# OutputIndicator.net
KiCad netlist of a schematic drawn in EAGLE
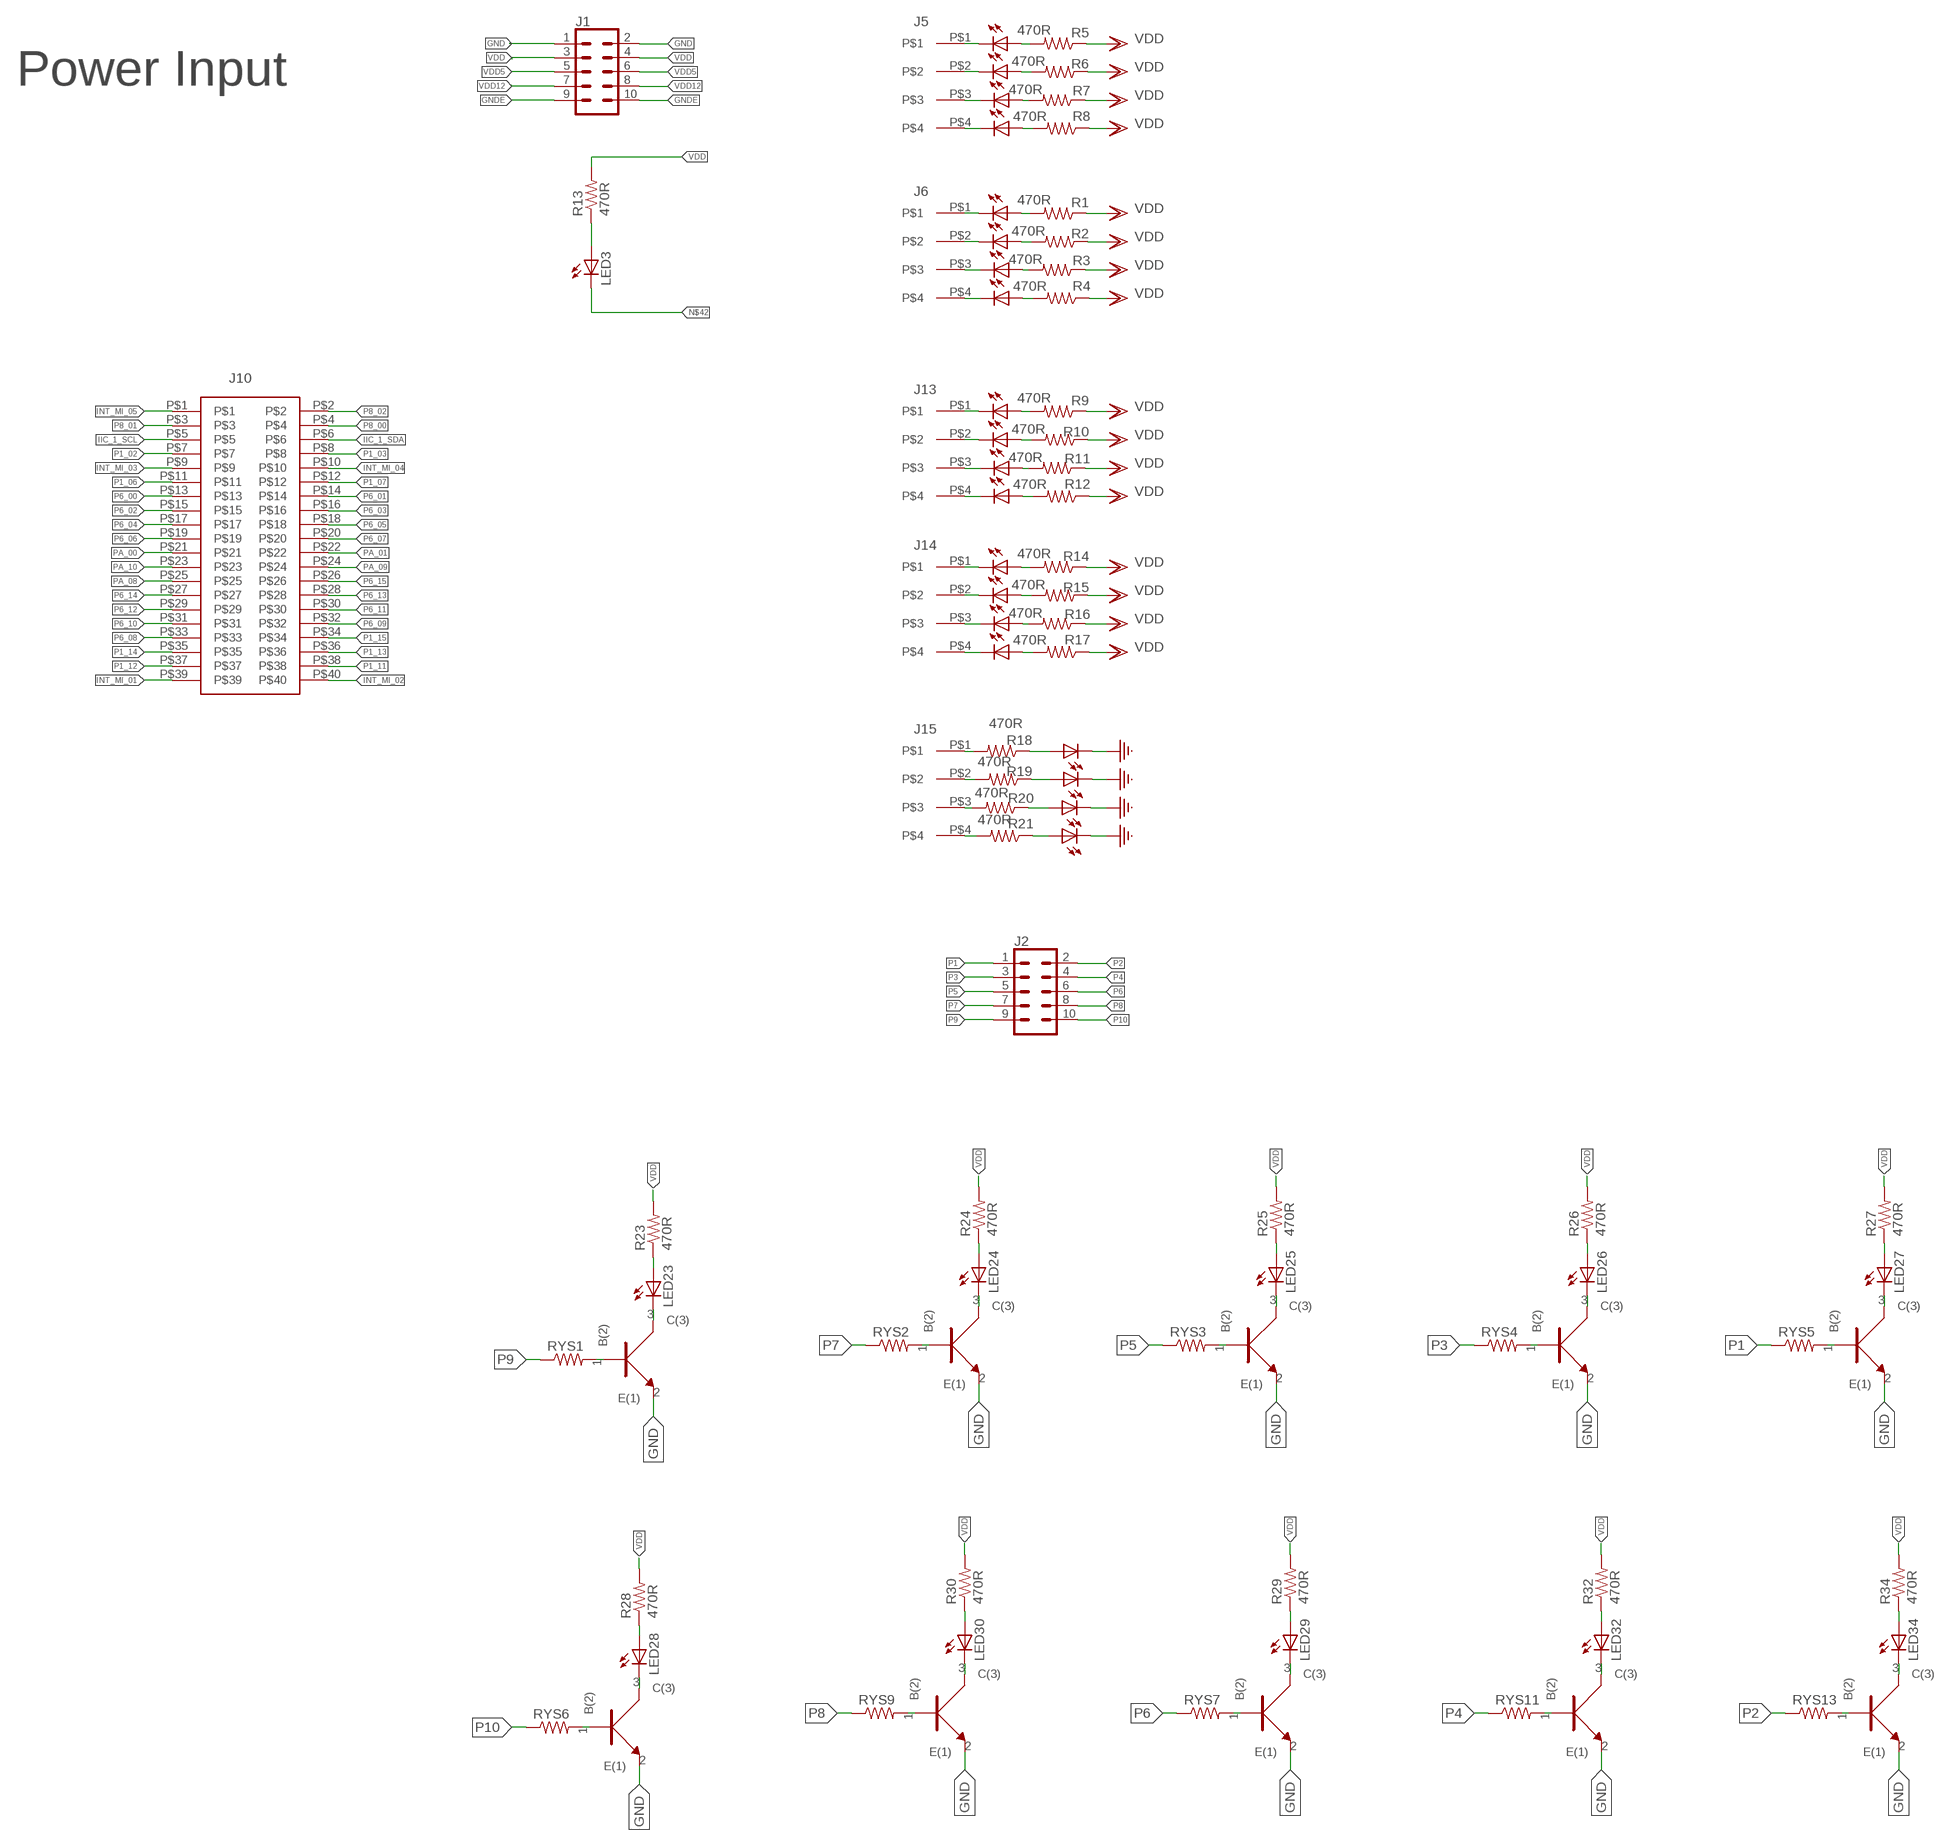
[diagram p0: schematic, sheet 1]

(export (version "E")
  (design (tool "Eeschema 10.0.6"))
  (components
    (comp (ref "J1")
      (value "CONN_05X2PTH")
      (footprint "eagle-import:2X5")
      (libsource (lib "eagle-import") (part "CONN_05X2PTH"))
    )
    (comp (ref "J2")
      (value "CONN_05X2NO_SILK")
      (footprint "eagle-import:2X5_NOSILK")
      (libsource (lib "eagle-import") (part "CONN_05X2NO_SILK"))
    )
    (comp (ref "J5")
      (value "3.81MM_1_X_4_RT_ANGLE_PLUG_HEADER")
      (footprint "eagle-import:1X4_3.81MM_PITCH")
      (libsource (lib "eagle-import") (part "3.81MM_1_X_4_RT_ANGLE_PLUG_HEADER"))
    )
    (comp (ref "J6")
      (value "3.81MM_1_X_4_RT_ANGLE_PLUG_HEADER")
      (footprint "eagle-import:1X4_3.81MM_PITCH")
      (libsource (lib "eagle-import") (part "3.81MM_1_X_4_RT_ANGLE_PLUG_HEADER"))
    )
    (comp (ref "J10")
      (value "HEADER_2_X_20_GENERIC")
      (footprint "eagle-import:HEADER_2_X_20_.1_INCH")
      (libsource (lib "eagle-import") (part "HEADER_2_X_20_GENERIC"))
    )
    (comp (ref "J13")
      (value "3.81MM_1_X_4_RT_ANGLE_PLUG_HEADER")
      (footprint "eagle-import:1X4_3.81MM_PITCH")
      (libsource (lib "eagle-import") (part "3.81MM_1_X_4_RT_ANGLE_PLUG_HEADER"))
    )
    (comp (ref "J14")
      (value "3.81MM_1_X_4_RT_ANGLE_PLUG_HEADER")
      (footprint "eagle-import:1X4_3.81MM_PITCH")
      (libsource (lib "eagle-import") (part "3.81MM_1_X_4_RT_ANGLE_PLUG_HEADER"))
    )
    (comp (ref "J15")
      (value "3.81MM_1_X_4_RT_ANGLE_PLUG_HEADER")
      (footprint "eagle-import:1X4_3.81MM_PITCH")
      (libsource (lib "eagle-import") (part "3.81MM_1_X_4_RT_ANGLE_PLUG_HEADER"))
    )
    (comp (ref "LED1")
      (value "LED_0805_GREEN")
      (footprint "eagle-import:LED_0805_GREEN")
      (libsource (lib "eagle-import") (part "LED_0805_GREEN"))
    )
    (comp (ref "LED2")
      (value "LED_0805_GREEN")
      (footprint "eagle-import:LED_0805_GREEN")
      (libsource (lib "eagle-import") (part "LED_0805_GREEN"))
    )
    (comp (ref "LED3")
      (value "LED_0805_GREEN")
      (footprint "eagle-import:LED_0805_GREEN")
      (libsource (lib "eagle-import") (part "LED_0805_GREEN"))
    )
    (comp (ref "LED4")
      (value "LED_0805_GREEN")
      (footprint "eagle-import:LED_0805_GREEN")
      (libsource (lib "eagle-import") (part "LED_0805_GREEN"))
    )
    (comp (ref "LED5")
      (value "LED_0805_GREEN")
      (footprint "eagle-import:LED_0805_GREEN")
      (libsource (lib "eagle-import") (part "LED_0805_GREEN"))
    )
    (comp (ref "LED6")
      (value "LED_0805_GREEN")
      (footprint "eagle-import:LED_0805_GREEN")
      (libsource (lib "eagle-import") (part "LED_0805_GREEN"))
    )
    (comp (ref "LED7")
      (value "LED_0805_GREEN")
      (footprint "eagle-import:LED_0805_GREEN")
      (libsource (lib "eagle-import") (part "LED_0805_GREEN"))
    )
    (comp (ref "LED8")
      (value "LED_0805_GREEN")
      (footprint "eagle-import:LED_0805_GREEN")
      (libsource (lib "eagle-import") (part "LED_0805_GREEN"))
    )
    (comp (ref "LED9")
      (value "LED_0805_GREEN")
      (footprint "eagle-import:LED_0805_GREEN")
      (libsource (lib "eagle-import") (part "LED_0805_GREEN"))
    )
    (comp (ref "LED10")
      (value "LED_0805_GREEN")
      (footprint "eagle-import:LED_0805_GREEN")
      (libsource (lib "eagle-import") (part "LED_0805_GREEN"))
    )
    (comp (ref "LED11")
      (value "LED_0805_GREEN")
      (footprint "eagle-import:LED_0805_GREEN")
      (libsource (lib "eagle-import") (part "LED_0805_GREEN"))
    )
    (comp (ref "LED12")
      (value "LED_0805_GREEN")
      (footprint "eagle-import:LED_0805_GREEN")
      (libsource (lib "eagle-import") (part "LED_0805_GREEN"))
    )
    (comp (ref "LED13")
      (value "LED_0805_GREEN")
      (footprint "eagle-import:LED_0805_GREEN")
      (libsource (lib "eagle-import") (part "LED_0805_GREEN"))
    )
    (comp (ref "LED14")
      (value "LED_0805_GREEN")
      (footprint "eagle-import:LED_0805_GREEN")
      (libsource (lib "eagle-import") (part "LED_0805_GREEN"))
    )
    (comp (ref "LED15")
      (value "LED_0805_GREEN")
      (footprint "eagle-import:LED_0805_GREEN")
      (libsource (lib "eagle-import") (part "LED_0805_GREEN"))
    )
    (comp (ref "LED16")
      (value "LED_0805_GREEN")
      (footprint "eagle-import:LED_0805_GREEN")
      (libsource (lib "eagle-import") (part "LED_0805_GREEN"))
    )
    (comp (ref "LED17")
      (value "LED_0805_GREEN")
      (footprint "eagle-import:LED_0805_GREEN")
      (libsource (lib "eagle-import") (part "LED_0805_GREEN"))
    )
    (comp (ref "LED18")
      (value "LED_0805_GREEN")
      (footprint "eagle-import:LED_0805_GREEN")
      (libsource (lib "eagle-import") (part "LED_0805_GREEN"))
    )
    (comp (ref "LED19")
      (value "LED_0805_GREEN")
      (footprint "eagle-import:LED_0805_GREEN")
      (libsource (lib "eagle-import") (part "LED_0805_GREEN"))
    )
    (comp (ref "LED20")
      (value "LED_0805_GREEN")
      (footprint "eagle-import:LED_0805_GREEN")
      (libsource (lib "eagle-import") (part "LED_0805_GREEN"))
    )
    (comp (ref "LED21")
      (value "LED_0805_GREEN")
      (footprint "eagle-import:LED_0805_GREEN")
      (libsource (lib "eagle-import") (part "LED_0805_GREEN"))
    )
    (comp (ref "LED23")
      (value "LED_0805_GREEN")
      (footprint "eagle-import:LED_0805_GREEN")
      (libsource (lib "eagle-import") (part "LED_0805_GREEN"))
    )
    (comp (ref "LED24")
      (value "LED_0805_GREEN")
      (footprint "eagle-import:LED_0805_GREEN")
      (libsource (lib "eagle-import") (part "LED_0805_GREEN"))
    )
    (comp (ref "LED25")
      (value "LED_0805_GREEN")
      (footprint "eagle-import:LED_0805_GREEN")
      (libsource (lib "eagle-import") (part "LED_0805_GREEN"))
    )
    (comp (ref "LED26")
      (value "LED_0805_GREEN")
      (footprint "eagle-import:LED_0805_GREEN")
      (libsource (lib "eagle-import") (part "LED_0805_GREEN"))
    )
    (comp (ref "LED27")
      (value "LED_0805_GREEN")
      (footprint "eagle-import:LED_0805_GREEN")
      (libsource (lib "eagle-import") (part "LED_0805_GREEN"))
    )
    (comp (ref "LED28")
      (value "LED_0805_GREEN")
      (footprint "eagle-import:LED_0805_GREEN")
      (libsource (lib "eagle-import") (part "LED_0805_GREEN"))
    )
    (comp (ref "LED29")
      (value "LED_0805_GREEN")
      (footprint "eagle-import:LED_0805_GREEN")
      (libsource (lib "eagle-import") (part "LED_0805_GREEN"))
    )
    (comp (ref "LED30")
      (value "LED_0805_GREEN")
      (footprint "eagle-import:LED_0805_GREEN")
      (libsource (lib "eagle-import") (part "LED_0805_GREEN"))
    )
    (comp (ref "LED32")
      (value "LED_0805_GREEN")
      (footprint "eagle-import:LED_0805_GREEN")
      (libsource (lib "eagle-import") (part "LED_0805_GREEN"))
    )
    (comp (ref "LED34")
      (value "LED_0805_GREEN")
      (footprint "eagle-import:LED_0805_GREEN")
      (libsource (lib "eagle-import") (part "LED_0805_GREEN"))
    )
    (comp (ref "R1")
      (value "470R")
      (footprint "eagle-import:0402")
      (libsource (lib "eagle-import") (part "R_0402"))
    )
    (comp (ref "R2")
      (value "470R")
      (footprint "eagle-import:0402")
      (libsource (lib "eagle-import") (part "R_0402"))
    )
    (comp (ref "R3")
      (value "470R")
      (footprint "eagle-import:0402")
      (libsource (lib "eagle-import") (part "R_0402"))
    )
    (comp (ref "R4")
      (value "470R")
      (footprint "eagle-import:0402")
      (libsource (lib "eagle-import") (part "R_0402"))
    )
    (comp (ref "R5")
      (value "470R")
      (footprint "eagle-import:0402")
      (libsource (lib "eagle-import") (part "R_0402"))
    )
    (comp (ref "R6")
      (value "470R")
      (footprint "eagle-import:0402")
      (libsource (lib "eagle-import") (part "R_0402"))
    )
    (comp (ref "R7")
      (value "470R")
      (footprint "eagle-import:0402")
      (libsource (lib "eagle-import") (part "R_0402"))
    )
    (comp (ref "R8")
      (value "470R")
      (footprint "eagle-import:0402")
      (libsource (lib "eagle-import") (part "R_0402"))
    )
    (comp (ref "R9")
      (value "470R")
      (footprint "eagle-import:0402")
      (libsource (lib "eagle-import") (part "R_0402"))
    )
    (comp (ref "R10")
      (value "470R")
      (footprint "eagle-import:0402")
      (libsource (lib "eagle-import") (part "R_0402"))
    )
    (comp (ref "R11")
      (value "470R")
      (footprint "eagle-import:0402")
      (libsource (lib "eagle-import") (part "R_0402"))
    )
    (comp (ref "R12")
      (value "470R")
      (footprint "eagle-import:0402")
      (libsource (lib "eagle-import") (part "R_0402"))
    )
    (comp (ref "R13")
      (value "470R")
      (footprint "eagle-import:0402")
      (libsource (lib "eagle-import") (part "R_0402"))
    )
    (comp (ref "R14")
      (value "470R")
      (footprint "eagle-import:0402")
      (libsource (lib "eagle-import") (part "R_0402"))
    )
    (comp (ref "R15")
      (value "470R")
      (footprint "eagle-import:0402")
      (libsource (lib "eagle-import") (part "R_0402"))
    )
    (comp (ref "R16")
      (value "470R")
      (footprint "eagle-import:0402")
      (libsource (lib "eagle-import") (part "R_0402"))
    )
    (comp (ref "R17")
      (value "470R")
      (footprint "eagle-import:0402")
      (libsource (lib "eagle-import") (part "R_0402"))
    )
    (comp (ref "R18")
      (value "470R")
      (footprint "eagle-import:0402")
      (libsource (lib "eagle-import") (part "R_0402"))
    )
    (comp (ref "R19")
      (value "470R")
      (footprint "eagle-import:0402")
      (libsource (lib "eagle-import") (part "R_0402"))
    )
    (comp (ref "R20")
      (value "470R")
      (footprint "eagle-import:0402")
      (libsource (lib "eagle-import") (part "R_0402"))
    )
    (comp (ref "R21")
      (value "470R")
      (footprint "eagle-import:0402")
      (libsource (lib "eagle-import") (part "R_0402"))
    )
    (comp (ref "R23")
      (value "470R")
      (footprint "eagle-import:0402")
      (libsource (lib "eagle-import") (part "R_0402"))
    )
    (comp (ref "R24")
      (value "470R")
      (footprint "eagle-import:0402")
      (libsource (lib "eagle-import") (part "R_0402"))
    )
    (comp (ref "R25")
      (value "470R")
      (footprint "eagle-import:0402")
      (libsource (lib "eagle-import") (part "R_0402"))
    )
    (comp (ref "R26")
      (value "470R")
      (footprint "eagle-import:0402")
      (libsource (lib "eagle-import") (part "R_0402"))
    )
    (comp (ref "R27")
      (value "470R")
      (footprint "eagle-import:0402")
      (libsource (lib "eagle-import") (part "R_0402"))
    )
    (comp (ref "R28")
      (value "470R")
      (footprint "eagle-import:0402")
      (libsource (lib "eagle-import") (part "R_0402"))
    )
    (comp (ref "R29")
      (value "470R")
      (footprint "eagle-import:0402")
      (libsource (lib "eagle-import") (part "R_0402"))
    )
    (comp (ref "R30")
      (value "470R")
      (footprint "eagle-import:0402")
      (libsource (lib "eagle-import") (part "R_0402"))
    )
    (comp (ref "R32")
      (value "470R")
      (footprint "eagle-import:0402")
      (libsource (lib "eagle-import") (part "R_0402"))
    )
    (comp (ref "R34")
      (value "470R")
      (footprint "eagle-import:0402")
      (libsource (lib "eagle-import") (part "R_0402"))
    )
    (comp (ref "RYS1")
      (value "1K")
      (footprint "eagle-import:0402")
      (libsource (lib "eagle-import") (part "R_0402"))
    )
    (comp (ref "RYS2")
      (value "1K")
      (footprint "eagle-import:0402")
      (libsource (lib "eagle-import") (part "R_0402"))
    )
    (comp (ref "RYS3")
      (value "1K")
      (footprint "eagle-import:0402")
      (libsource (lib "eagle-import") (part "R_0402"))
    )
    (comp (ref "RYS4")
      (value "1K")
      (footprint "eagle-import:0402")
      (libsource (lib "eagle-import") (part "R_0402"))
    )
    (comp (ref "RYS5")
      (value "1K")
      (footprint "eagle-import:0402")
      (libsource (lib "eagle-import") (part "R_0402"))
    )
    (comp (ref "RYS6")
      (value "1K")
      (footprint "eagle-import:0402")
      (libsource (lib "eagle-import") (part "R_0402"))
    )
    (comp (ref "RYS7")
      (value "1K")
      (footprint "eagle-import:0402")
      (libsource (lib "eagle-import") (part "R_0402"))
    )
    (comp (ref "RYS9")
      (value "1K")
      (footprint "eagle-import:0402")
      (libsource (lib "eagle-import") (part "R_0402"))
    )
    (comp (ref "RYS11")
      (value "1K")
      (footprint "eagle-import:0402")
      (libsource (lib "eagle-import") (part "R_0402"))
    )
    (comp (ref "RYS13")
      (value "1K")
      (footprint "eagle-import:0402")
      (libsource (lib "eagle-import") (part "R_0402"))
    )
    (comp (ref "U1")
      (value "BC846BW")
      (footprint "eagle-import:SOT323")
      (libsource (lib "eagle-import") (part "BC846BW"))
    )
    (comp (ref "U2")
      (value "BC846BW")
      (footprint "eagle-import:SOT323")
      (libsource (lib "eagle-import") (part "BC846BW"))
    )
    (comp (ref "U3")
      (value "BC846BW")
      (footprint "eagle-import:SOT323")
      (libsource (lib "eagle-import") (part "BC846BW"))
    )
    (comp (ref "U4")
      (value "BC846BW")
      (footprint "eagle-import:SOT323")
      (libsource (lib "eagle-import") (part "BC846BW"))
    )
    (comp (ref "U5")
      (value "BC846BW")
      (footprint "eagle-import:SOT323")
      (libsource (lib "eagle-import") (part "BC846BW"))
    )
    (comp (ref "U6")
      (value "BC846BW")
      (footprint "eagle-import:SOT323")
      (libsource (lib "eagle-import") (part "BC846BW"))
    )
    (comp (ref "U7")
      (value "BC846BW")
      (footprint "eagle-import:SOT323")
      (libsource (lib "eagle-import") (part "BC846BW"))
    )
    (comp (ref "U8")
      (value "BC846BW")
      (footprint "eagle-import:SOT323")
      (libsource (lib "eagle-import") (part "BC846BW"))
    )
    (comp (ref "U10")
      (value "BC846BW")
      (footprint "eagle-import:SOT323")
      (libsource (lib "eagle-import") (part "BC846BW"))
    )
    (comp (ref "U12")
      (value "BC846BW")
      (footprint "eagle-import:SOT323")
      (libsource (lib "eagle-import") (part "BC846BW"))
    )
  )
  (nets
    (net (code "1") (name "GND") (class "Default")
      (node (ref "J1") (pin "1") (pinfunction "1_1") (pintype "passive"))
      (node (ref "J1") (pin "2") (pinfunction "2_2") (pintype "passive"))
      (node (ref "LED18") (pin "C") (pinfunction "C_C") (pintype "passive"))
      (node (ref "LED19") (pin "C") (pinfunction "C_C") (pintype "passive"))
      (node (ref "LED20") (pin "C") (pinfunction "C_C") (pintype "passive"))
      (node (ref "LED21") (pin "C") (pinfunction "C_C") (pintype "passive"))
      (node (ref "U1") (pin "2") (pinfunction "E(1)_2") (pintype "output"))
      (node (ref "U10") (pin "2") (pinfunction "E(1)_2") (pintype "output"))
      (node (ref "U12") (pin "2") (pinfunction "E(1)_2") (pintype "output"))
      (node (ref "U2") (pin "2") (pinfunction "E(1)_2") (pintype "output"))
      (node (ref "U3") (pin "2") (pinfunction "E(1)_2") (pintype "output"))
      (node (ref "U4") (pin "2") (pinfunction "E(1)_2") (pintype "output"))
      (node (ref "U5") (pin "2") (pinfunction "E(1)_2") (pintype "output"))
      (node (ref "U6") (pin "2") (pinfunction "E(1)_2") (pintype "output"))
      (node (ref "U7") (pin "2") (pinfunction "E(1)_2") (pintype "output"))
      (node (ref "U8") (pin "2") (pinfunction "E(1)_2") (pintype "output"))
    )
    (net (code "2") (name "GNDE") (class "Default")
      (node (ref "J1") (pin "10") (pinfunction "10_10") (pintype "passive"))
      (node (ref "J1") (pin "9") (pinfunction "9_9") (pintype "passive"))
    )
    (net (code "3") (name "IIC_1_SCL") (class "Default")
      (node (ref "J10") (pin "P$5") (pinfunction "P$5_P$5") (pintype "bidirectional"))
    )
    (net (code "4") (name "IIC_1_SDA") (class "Default")
      (node (ref "J10") (pin "P$6") (pinfunction "P$6_P$6") (pintype "bidirectional"))
    )
    (net (code "5") (name "INT_MI_01") (class "Default")
      (node (ref "J10") (pin "P$39") (pinfunction "P$39_P$39") (pintype "bidirectional"))
    )
    (net (code "6") (name "INT_MI_02") (class "Default")
      (node (ref "J10") (pin "P$40") (pinfunction "P$40_P$40") (pintype "bidirectional"))
    )
    (net (code "7") (name "INT_MI_03") (class "Default")
      (node (ref "J10") (pin "P$9") (pinfunction "P$9_P$9") (pintype "bidirectional"))
    )
    (net (code "8") (name "INT_MI_04") (class "Default")
      (node (ref "J10") (pin "P$10") (pinfunction "P$10_P$10") (pintype "bidirectional"))
    )
    (net (code "9") (name "INT_MI_05") (class "Default")
      (node (ref "J10") (pin "P$1") (pinfunction "P$1_P$1") (pintype "bidirectional"))
    )
    (net (code "10") (name "N$42") (class "Default")
      (node (ref "LED3") (pin "C") (pinfunction "C_C") (pintype "passive"))
    )
    (net (code "11") (name "Net-(J5-PadP$1)") (class "Default")
      (node (ref "J5") (pin "P$1") (pinfunction "P$1_P$1") (pintype "bidirectional"))
      (node (ref "LED6") (pin "C") (pinfunction "C_C") (pintype "passive"))
    )
    (net (code "12") (name "Net-(J5-PadP$2)") (class "Default")
      (node (ref "J5") (pin "P$2") (pinfunction "P$2_P$2") (pintype "bidirectional"))
      (node (ref "LED7") (pin "C") (pinfunction "C_C") (pintype "passive"))
    )
    (net (code "13") (name "Net-(J5-PadP$3)") (class "Default")
      (node (ref "J5") (pin "P$3") (pinfunction "P$3_P$3") (pintype "bidirectional"))
      (node (ref "LED8") (pin "C") (pinfunction "C_C") (pintype "passive"))
    )
    (net (code "14") (name "Net-(J5-PadP$4)") (class "Default")
      (node (ref "J5") (pin "P$4") (pinfunction "P$4_P$4") (pintype "bidirectional"))
      (node (ref "LED9") (pin "C") (pinfunction "C_C") (pintype "passive"))
    )
    (net (code "15") (name "Net-(J6-PadP$1)") (class "Default")
      (node (ref "J6") (pin "P$1") (pinfunction "P$1_P$1") (pintype "bidirectional"))
      (node (ref "LED1") (pin "C") (pinfunction "C_C") (pintype "passive"))
    )
    (net (code "16") (name "Net-(J6-PadP$2)") (class "Default")
      (node (ref "J6") (pin "P$2") (pinfunction "P$2_P$2") (pintype "bidirectional"))
      (node (ref "LED2") (pin "C") (pinfunction "C_C") (pintype "passive"))
    )
    (net (code "17") (name "Net-(J6-PadP$3)") (class "Default")
      (node (ref "J6") (pin "P$3") (pinfunction "P$3_P$3") (pintype "bidirectional"))
      (node (ref "LED4") (pin "C") (pinfunction "C_C") (pintype "passive"))
    )
    (net (code "18") (name "Net-(J6-PadP$4)") (class "Default")
      (node (ref "J6") (pin "P$4") (pinfunction "P$4_P$4") (pintype "bidirectional"))
      (node (ref "LED5") (pin "C") (pinfunction "C_C") (pintype "passive"))
    )
    (net (code "19") (name "Net-(J13-PadP$1)") (class "Default")
      (node (ref "J13") (pin "P$1") (pinfunction "P$1_P$1") (pintype "bidirectional"))
      (node (ref "LED10") (pin "C") (pinfunction "C_C") (pintype "passive"))
    )
    (net (code "20") (name "Net-(J13-PadP$2)") (class "Default")
      (node (ref "J13") (pin "P$2") (pinfunction "P$2_P$2") (pintype "bidirectional"))
      (node (ref "LED11") (pin "C") (pinfunction "C_C") (pintype "passive"))
    )
    (net (code "21") (name "Net-(J13-PadP$3)") (class "Default")
      (node (ref "J13") (pin "P$3") (pinfunction "P$3_P$3") (pintype "bidirectional"))
      (node (ref "LED12") (pin "C") (pinfunction "C_C") (pintype "passive"))
    )
    (net (code "22") (name "Net-(J13-PadP$4)") (class "Default")
      (node (ref "J13") (pin "P$4") (pinfunction "P$4_P$4") (pintype "bidirectional"))
      (node (ref "LED13") (pin "C") (pinfunction "C_C") (pintype "passive"))
    )
    (net (code "23") (name "Net-(J14-PadP$1)") (class "Default")
      (node (ref "J14") (pin "P$1") (pinfunction "P$1_P$1") (pintype "bidirectional"))
      (node (ref "LED14") (pin "C") (pinfunction "C_C") (pintype "passive"))
    )
    (net (code "24") (name "Net-(J14-PadP$2)") (class "Default")
      (node (ref "J14") (pin "P$2") (pinfunction "P$2_P$2") (pintype "bidirectional"))
      (node (ref "LED15") (pin "C") (pinfunction "C_C") (pintype "passive"))
    )
    (net (code "25") (name "Net-(J14-PadP$3)") (class "Default")
      (node (ref "J14") (pin "P$3") (pinfunction "P$3_P$3") (pintype "bidirectional"))
      (node (ref "LED16") (pin "C") (pinfunction "C_C") (pintype "passive"))
    )
    (net (code "26") (name "Net-(J14-PadP$4)") (class "Default")
      (node (ref "J14") (pin "P$4") (pinfunction "P$4_P$4") (pintype "bidirectional"))
      (node (ref "LED17") (pin "C") (pinfunction "C_C") (pintype "passive"))
    )
    (net (code "27") (name "Net-(R1-2)") (class "Default")
      (node (ref "LED1") (pin "A") (pinfunction "A_A") (pintype "passive"))
      (node (ref "R1") (pin "P$2") (pinfunction "2_P$2") (pintype "passive"))
    )
    (net (code "28") (name "Net-(R2-2)") (class "Default")
      (node (ref "LED2") (pin "A") (pinfunction "A_A") (pintype "passive"))
      (node (ref "R2") (pin "P$2") (pinfunction "2_P$2") (pintype "passive"))
    )
    (net (code "29") (name "Net-(R3-2)") (class "Default")
      (node (ref "LED4") (pin "A") (pinfunction "A_A") (pintype "passive"))
      (node (ref "R3") (pin "P$2") (pinfunction "2_P$2") (pintype "passive"))
    )
    (net (code "30") (name "Net-(R4-2)") (class "Default")
      (node (ref "LED5") (pin "A") (pinfunction "A_A") (pintype "passive"))
      (node (ref "R4") (pin "P$2") (pinfunction "2_P$2") (pintype "passive"))
    )
    (net (code "31") (name "Net-(R5-2)") (class "Default")
      (node (ref "LED6") (pin "A") (pinfunction "A_A") (pintype "passive"))
      (node (ref "R5") (pin "P$2") (pinfunction "2_P$2") (pintype "passive"))
    )
    (net (code "32") (name "Net-(R6-2)") (class "Default")
      (node (ref "LED7") (pin "A") (pinfunction "A_A") (pintype "passive"))
      (node (ref "R6") (pin "P$2") (pinfunction "2_P$2") (pintype "passive"))
    )
    (net (code "33") (name "Net-(R7-2)") (class "Default")
      (node (ref "LED8") (pin "A") (pinfunction "A_A") (pintype "passive"))
      (node (ref "R7") (pin "P$2") (pinfunction "2_P$2") (pintype "passive"))
    )
    (net (code "34") (name "Net-(R8-2)") (class "Default")
      (node (ref "LED9") (pin "A") (pinfunction "A_A") (pintype "passive"))
      (node (ref "R8") (pin "P$2") (pinfunction "2_P$2") (pintype "passive"))
    )
    (net (code "35") (name "Net-(R9-2)") (class "Default")
      (node (ref "LED10") (pin "A") (pinfunction "A_A") (pintype "passive"))
      (node (ref "R9") (pin "P$2") (pinfunction "2_P$2") (pintype "passive"))
    )
    (net (code "36") (name "Net-(R10-2)") (class "Default")
      (node (ref "LED11") (pin "A") (pinfunction "A_A") (pintype "passive"))
      (node (ref "R10") (pin "P$2") (pinfunction "2_P$2") (pintype "passive"))
    )
    (net (code "37") (name "Net-(R11-2)") (class "Default")
      (node (ref "LED12") (pin "A") (pinfunction "A_A") (pintype "passive"))
      (node (ref "R11") (pin "P$2") (pinfunction "2_P$2") (pintype "passive"))
    )
    (net (code "38") (name "Net-(R12-2)") (class "Default")
      (node (ref "LED13") (pin "A") (pinfunction "A_A") (pintype "passive"))
      (node (ref "R12") (pin "P$2") (pinfunction "2_P$2") (pintype "passive"))
    )
    (net (code "39") (name "Net-(R13-1)") (class "Default")
      (node (ref "LED3") (pin "A") (pinfunction "A_A") (pintype "passive"))
      (node (ref "R13") (pin "P$1") (pinfunction "1_P$1") (pintype "passive"))
    )
    (net (code "40") (name "Net-(R14-2)") (class "Default")
      (node (ref "LED14") (pin "A") (pinfunction "A_A") (pintype "passive"))
      (node (ref "R14") (pin "P$2") (pinfunction "2_P$2") (pintype "passive"))
    )
    (net (code "41") (name "Net-(R15-2)") (class "Default")
      (node (ref "LED15") (pin "A") (pinfunction "A_A") (pintype "passive"))
      (node (ref "R15") (pin "P$2") (pinfunction "2_P$2") (pintype "passive"))
    )
    (net (code "42") (name "Net-(R16-2)") (class "Default")
      (node (ref "LED16") (pin "A") (pinfunction "A_A") (pintype "passive"))
      (node (ref "R16") (pin "P$2") (pinfunction "2_P$2") (pintype "passive"))
    )
    (net (code "43") (name "Net-(R17-2)") (class "Default")
      (node (ref "LED17") (pin "A") (pinfunction "A_A") (pintype "passive"))
      (node (ref "R17") (pin "P$2") (pinfunction "2_P$2") (pintype "passive"))
    )
    (net (code "44") (name "Net-(R18-1)") (class "Default")
      (node (ref "LED18") (pin "A") (pinfunction "A_A") (pintype "passive"))
      (node (ref "R18") (pin "P$1") (pinfunction "1_P$1") (pintype "passive"))
    )
    (net (code "45") (name "Net-(R18-2)") (class "Default")
      (node (ref "J15") (pin "P$1") (pinfunction "P$1_P$1") (pintype "bidirectional"))
      (node (ref "R18") (pin "P$2") (pinfunction "2_P$2") (pintype "passive"))
    )
    (net (code "46") (name "Net-(R19-1)") (class "Default")
      (node (ref "LED19") (pin "A") (pinfunction "A_A") (pintype "passive"))
      (node (ref "R19") (pin "P$1") (pinfunction "1_P$1") (pintype "passive"))
    )
    (net (code "47") (name "Net-(R19-2)") (class "Default")
      (node (ref "J15") (pin "P$2") (pinfunction "P$2_P$2") (pintype "bidirectional"))
      (node (ref "R19") (pin "P$2") (pinfunction "2_P$2") (pintype "passive"))
    )
    (net (code "48") (name "Net-(R20-1)") (class "Default")
      (node (ref "LED20") (pin "A") (pinfunction "A_A") (pintype "passive"))
      (node (ref "R20") (pin "P$1") (pinfunction "1_P$1") (pintype "passive"))
    )
    (net (code "49") (name "Net-(R20-2)") (class "Default")
      (node (ref "J15") (pin "P$3") (pinfunction "P$3_P$3") (pintype "bidirectional"))
      (node (ref "R20") (pin "P$2") (pinfunction "2_P$2") (pintype "passive"))
    )
    (net (code "50") (name "Net-(R21-1)") (class "Default")
      (node (ref "LED21") (pin "A") (pinfunction "A_A") (pintype "passive"))
      (node (ref "R21") (pin "P$1") (pinfunction "1_P$1") (pintype "passive"))
    )
    (net (code "51") (name "Net-(R21-2)") (class "Default")
      (node (ref "J15") (pin "P$4") (pinfunction "P$4_P$4") (pintype "bidirectional"))
      (node (ref "R21") (pin "P$2") (pinfunction "2_P$2") (pintype "passive"))
    )
    (net (code "52") (name "Net-(R23-1)") (class "Default")
      (node (ref "LED23") (pin "A") (pinfunction "A_A") (pintype "passive"))
      (node (ref "R23") (pin "P$1") (pinfunction "1_P$1") (pintype "passive"))
    )
    (net (code "53") (name "Net-(R24-1)") (class "Default")
      (node (ref "LED24") (pin "A") (pinfunction "A_A") (pintype "passive"))
      (node (ref "R24") (pin "P$1") (pinfunction "1_P$1") (pintype "passive"))
    )
    (net (code "54") (name "Net-(R25-1)") (class "Default")
      (node (ref "LED25") (pin "A") (pinfunction "A_A") (pintype "passive"))
      (node (ref "R25") (pin "P$1") (pinfunction "1_P$1") (pintype "passive"))
    )
    (net (code "55") (name "Net-(R26-1)") (class "Default")
      (node (ref "LED26") (pin "A") (pinfunction "A_A") (pintype "passive"))
      (node (ref "R26") (pin "P$1") (pinfunction "1_P$1") (pintype "passive"))
    )
    (net (code "56") (name "Net-(R27-1)") (class "Default")
      (node (ref "LED27") (pin "A") (pinfunction "A_A") (pintype "passive"))
      (node (ref "R27") (pin "P$1") (pinfunction "1_P$1") (pintype "passive"))
    )
    (net (code "57") (name "Net-(R28-1)") (class "Default")
      (node (ref "LED28") (pin "A") (pinfunction "A_A") (pintype "passive"))
      (node (ref "R28") (pin "P$1") (pinfunction "1_P$1") (pintype "passive"))
    )
    (net (code "58") (name "Net-(R29-1)") (class "Default")
      (node (ref "LED29") (pin "A") (pinfunction "A_A") (pintype "passive"))
      (node (ref "R29") (pin "P$1") (pinfunction "1_P$1") (pintype "passive"))
    )
    (net (code "59") (name "Net-(R30-1)") (class "Default")
      (node (ref "LED30") (pin "A") (pinfunction "A_A") (pintype "passive"))
      (node (ref "R30") (pin "P$1") (pinfunction "1_P$1") (pintype "passive"))
    )
    (net (code "60") (name "Net-(R32-1)") (class "Default")
      (node (ref "LED32") (pin "A") (pinfunction "A_A") (pintype "passive"))
      (node (ref "R32") (pin "P$1") (pinfunction "1_P$1") (pintype "passive"))
    )
    (net (code "61") (name "Net-(R34-1)") (class "Default")
      (node (ref "LED34") (pin "A") (pinfunction "A_A") (pintype "passive"))
      (node (ref "R34") (pin "P$1") (pinfunction "1_P$1") (pintype "passive"))
    )
    (net (code "62") (name "Net-(RYS1-2)") (class "Default")
      (node (ref "RYS1") (pin "P$2") (pinfunction "2_P$2") (pintype "passive"))
      (node (ref "U1") (pin "1") (pinfunction "B(2)_1") (pintype "input"))
    )
    (net (code "63") (name "Net-(RYS2-2)") (class "Default")
      (node (ref "RYS2") (pin "P$2") (pinfunction "2_P$2") (pintype "passive"))
      (node (ref "U2") (pin "1") (pinfunction "B(2)_1") (pintype "input"))
    )
    (net (code "64") (name "Net-(RYS3-2)") (class "Default")
      (node (ref "RYS3") (pin "P$2") (pinfunction "2_P$2") (pintype "passive"))
      (node (ref "U3") (pin "1") (pinfunction "B(2)_1") (pintype "input"))
    )
    (net (code "65") (name "Net-(RYS4-2)") (class "Default")
      (node (ref "RYS4") (pin "P$2") (pinfunction "2_P$2") (pintype "passive"))
      (node (ref "U4") (pin "1") (pinfunction "B(2)_1") (pintype "input"))
    )
    (net (code "66") (name "Net-(RYS5-2)") (class "Default")
      (node (ref "RYS5") (pin "P$2") (pinfunction "2_P$2") (pintype "passive"))
      (node (ref "U5") (pin "1") (pinfunction "B(2)_1") (pintype "input"))
    )
    (net (code "67") (name "Net-(RYS6-2)") (class "Default")
      (node (ref "RYS6") (pin "P$2") (pinfunction "2_P$2") (pintype "passive"))
      (node (ref "U6") (pin "1") (pinfunction "B(2)_1") (pintype "input"))
    )
    (net (code "68") (name "Net-(RYS7-2)") (class "Default")
      (node (ref "RYS7") (pin "P$2") (pinfunction "2_P$2") (pintype "passive"))
      (node (ref "U7") (pin "1") (pinfunction "B(2)_1") (pintype "input"))
    )
    (net (code "69") (name "Net-(RYS9-2)") (class "Default")
      (node (ref "RYS9") (pin "P$2") (pinfunction "2_P$2") (pintype "passive"))
      (node (ref "U8") (pin "1") (pinfunction "B(2)_1") (pintype "input"))
    )
    (net (code "70") (name "Net-(RYS11-2)") (class "Default")
      (node (ref "RYS11") (pin "P$2") (pinfunction "2_P$2") (pintype "passive"))
      (node (ref "U10") (pin "1") (pinfunction "B(2)_1") (pintype "input"))
    )
    (net (code "71") (name "Net-(RYS13-2)") (class "Default")
      (node (ref "RYS13") (pin "P$2") (pinfunction "2_P$2") (pintype "passive"))
      (node (ref "U12") (pin "1") (pinfunction "B(2)_1") (pintype "input"))
    )
    (net (code "72") (name "Net-(U1-C(3))") (class "Default")
      (node (ref "LED23") (pin "C") (pinfunction "C_C") (pintype "passive"))
      (node (ref "U1") (pin "3") (pinfunction "C(3)_3") (pintype "input"))
    )
    (net (code "73") (name "Net-(U2-C(3))") (class "Default")
      (node (ref "LED24") (pin "C") (pinfunction "C_C") (pintype "passive"))
      (node (ref "U2") (pin "3") (pinfunction "C(3)_3") (pintype "input"))
    )
    (net (code "74") (name "Net-(U3-C(3))") (class "Default")
      (node (ref "LED25") (pin "C") (pinfunction "C_C") (pintype "passive"))
      (node (ref "U3") (pin "3") (pinfunction "C(3)_3") (pintype "input"))
    )
    (net (code "75") (name "Net-(U4-C(3))") (class "Default")
      (node (ref "LED26") (pin "C") (pinfunction "C_C") (pintype "passive"))
      (node (ref "U4") (pin "3") (pinfunction "C(3)_3") (pintype "input"))
    )
    (net (code "76") (name "Net-(U5-C(3))") (class "Default")
      (node (ref "LED27") (pin "C") (pinfunction "C_C") (pintype "passive"))
      (node (ref "U5") (pin "3") (pinfunction "C(3)_3") (pintype "input"))
    )
    (net (code "77") (name "Net-(U6-C(3))") (class "Default")
      (node (ref "LED28") (pin "C") (pinfunction "C_C") (pintype "passive"))
      (node (ref "U6") (pin "3") (pinfunction "C(3)_3") (pintype "input"))
    )
    (net (code "78") (name "Net-(U7-C(3))") (class "Default")
      (node (ref "LED29") (pin "C") (pinfunction "C_C") (pintype "passive"))
      (node (ref "U7") (pin "3") (pinfunction "C(3)_3") (pintype "input"))
    )
    (net (code "79") (name "Net-(U8-C(3))") (class "Default")
      (node (ref "LED30") (pin "C") (pinfunction "C_C") (pintype "passive"))
      (node (ref "U8") (pin "3") (pinfunction "C(3)_3") (pintype "input"))
    )
    (net (code "80") (name "Net-(U10-C(3))") (class "Default")
      (node (ref "LED32") (pin "C") (pinfunction "C_C") (pintype "passive"))
      (node (ref "U10") (pin "3") (pinfunction "C(3)_3") (pintype "input"))
    )
    (net (code "81") (name "Net-(U12-C(3))") (class "Default")
      (node (ref "LED34") (pin "C") (pinfunction "C_C") (pintype "passive"))
      (node (ref "U12") (pin "3") (pinfunction "C(3)_3") (pintype "input"))
    )
    (net (code "82") (name "P1") (class "Default")
      (node (ref "J2") (pin "1") (pinfunction "1_1") (pintype "passive"))
      (node (ref "RYS5") (pin "P$1") (pinfunction "1_P$1") (pintype "passive"))
    )
    (net (code "83") (name "P1_02") (class "Default")
      (node (ref "J10") (pin "P$7") (pinfunction "P$7_P$7") (pintype "bidirectional"))
    )
    (net (code "84") (name "P1_03") (class "Default")
      (node (ref "J10") (pin "P$8") (pinfunction "P$8_P$8") (pintype "bidirectional"))
    )
    (net (code "85") (name "P1_06") (class "Default")
      (node (ref "J10") (pin "P$11") (pinfunction "P$11_P$11") (pintype "bidirectional"))
    )
    (net (code "86") (name "P1_07") (class "Default")
      (node (ref "J10") (pin "P$12") (pinfunction "P$12_P$12") (pintype "bidirectional"))
    )
    (net (code "87") (name "P1_11") (class "Default")
      (node (ref "J10") (pin "P$38") (pinfunction "P$38_P$38") (pintype "bidirectional"))
    )
    (net (code "88") (name "P1_12") (class "Default")
      (node (ref "J10") (pin "P$37") (pinfunction "P$37_P$37") (pintype "bidirectional"))
    )
    (net (code "89") (name "P1_13") (class "Default")
      (node (ref "J10") (pin "P$36") (pinfunction "P$36_P$36") (pintype "bidirectional"))
    )
    (net (code "90") (name "P1_14") (class "Default")
      (node (ref "J10") (pin "P$35") (pinfunction "P$35_P$35") (pintype "bidirectional"))
    )
    (net (code "91") (name "P1_15") (class "Default")
      (node (ref "J10") (pin "P$34") (pinfunction "P$34_P$34") (pintype "bidirectional"))
    )
    (net (code "92") (name "P2") (class "Default")
      (node (ref "J2") (pin "2") (pinfunction "2_2") (pintype "passive"))
      (node (ref "RYS13") (pin "P$1") (pinfunction "1_P$1") (pintype "passive"))
    )
    (net (code "93") (name "P3") (class "Default")
      (node (ref "J2") (pin "3") (pinfunction "3_3") (pintype "passive"))
      (node (ref "RYS4") (pin "P$1") (pinfunction "1_P$1") (pintype "passive"))
    )
    (net (code "94") (name "P4") (class "Default")
      (node (ref "J2") (pin "4") (pinfunction "4_4") (pintype "passive"))
      (node (ref "RYS11") (pin "P$1") (pinfunction "1_P$1") (pintype "passive"))
    )
    (net (code "95") (name "P5") (class "Default")
      (node (ref "J2") (pin "5") (pinfunction "5_5") (pintype "passive"))
      (node (ref "RYS3") (pin "P$1") (pinfunction "1_P$1") (pintype "passive"))
    )
    (net (code "96") (name "P6") (class "Default")
      (node (ref "J2") (pin "6") (pinfunction "6_6") (pintype "passive"))
      (node (ref "RYS7") (pin "P$1") (pinfunction "1_P$1") (pintype "passive"))
    )
    (net (code "97") (name "P6_00") (class "Default")
      (node (ref "J10") (pin "P$13") (pinfunction "P$13_P$13") (pintype "bidirectional"))
    )
    (net (code "98") (name "P6_01") (class "Default")
      (node (ref "J10") (pin "P$14") (pinfunction "P$14_P$14") (pintype "bidirectional"))
    )
    (net (code "99") (name "P6_02") (class "Default")
      (node (ref "J10") (pin "P$15") (pinfunction "P$15_P$15") (pintype "bidirectional"))
    )
    (net (code "100") (name "P6_03") (class "Default")
      (node (ref "J10") (pin "P$16") (pinfunction "P$16_P$16") (pintype "bidirectional"))
    )
    (net (code "101") (name "P6_04") (class "Default")
      (node (ref "J10") (pin "P$17") (pinfunction "P$17_P$17") (pintype "bidirectional"))
    )
    (net (code "102") (name "P6_05") (class "Default")
      (node (ref "J10") (pin "P$18") (pinfunction "P$18_P$18") (pintype "bidirectional"))
    )
    (net (code "103") (name "P6_06") (class "Default")
      (node (ref "J10") (pin "P$19") (pinfunction "P$19_P$19") (pintype "bidirectional"))
    )
    (net (code "104") (name "P6_07") (class "Default")
      (node (ref "J10") (pin "P$20") (pinfunction "P$20_P$20") (pintype "bidirectional"))
    )
    (net (code "105") (name "P6_08") (class "Default")
      (node (ref "J10") (pin "P$33") (pinfunction "P$33_P$33") (pintype "bidirectional"))
    )
    (net (code "106") (name "P6_09") (class "Default")
      (node (ref "J10") (pin "P$32") (pinfunction "P$32_P$32") (pintype "bidirectional"))
    )
    (net (code "107") (name "P6_10") (class "Default")
      (node (ref "J10") (pin "P$31") (pinfunction "P$31_P$31") (pintype "bidirectional"))
    )
    (net (code "108") (name "P6_11") (class "Default")
      (node (ref "J10") (pin "P$30") (pinfunction "P$30_P$30") (pintype "bidirectional"))
    )
    (net (code "109") (name "P6_12") (class "Default")
      (node (ref "J10") (pin "P$29") (pinfunction "P$29_P$29") (pintype "bidirectional"))
    )
    (net (code "110") (name "P6_13") (class "Default")
      (node (ref "J10") (pin "P$28") (pinfunction "P$28_P$28") (pintype "bidirectional"))
    )
    (net (code "111") (name "P6_14") (class "Default")
      (node (ref "J10") (pin "P$27") (pinfunction "P$27_P$27") (pintype "bidirectional"))
    )
    (net (code "112") (name "P6_15") (class "Default")
      (node (ref "J10") (pin "P$26") (pinfunction "P$26_P$26") (pintype "bidirectional"))
    )
    (net (code "113") (name "P7") (class "Default")
      (node (ref "J2") (pin "7") (pinfunction "7_7") (pintype "passive"))
      (node (ref "RYS2") (pin "P$1") (pinfunction "1_P$1") (pintype "passive"))
    )
    (net (code "114") (name "P8") (class "Default")
      (node (ref "J2") (pin "8") (pinfunction "8_8") (pintype "passive"))
      (node (ref "RYS9") (pin "P$1") (pinfunction "1_P$1") (pintype "passive"))
    )
    (net (code "115") (name "P8_00") (class "Default")
      (node (ref "J10") (pin "P$4") (pinfunction "P$4_P$4") (pintype "bidirectional"))
    )
    (net (code "116") (name "P8_01") (class "Default")
      (node (ref "J10") (pin "P$3") (pinfunction "P$3_P$3") (pintype "bidirectional"))
    )
    (net (code "117") (name "P8_02") (class "Default")
      (node (ref "J10") (pin "P$2") (pinfunction "P$2_P$2") (pintype "bidirectional"))
    )
    (net (code "118") (name "P9") (class "Default")
      (node (ref "J2") (pin "9") (pinfunction "9_9") (pintype "passive"))
      (node (ref "RYS1") (pin "P$1") (pinfunction "1_P$1") (pintype "passive"))
    )
    (net (code "119") (name "P10") (class "Default")
      (node (ref "J2") (pin "10") (pinfunction "10_10") (pintype "passive"))
      (node (ref "RYS6") (pin "P$1") (pinfunction "1_P$1") (pintype "passive"))
    )
    (net (code "120") (name "PA_00") (class "Default")
      (node (ref "J10") (pin "P$21") (pinfunction "P$21_P$21") (pintype "bidirectional"))
    )
    (net (code "121") (name "PA_01") (class "Default")
      (node (ref "J10") (pin "P$22") (pinfunction "P$22_P$22") (pintype "bidirectional"))
    )
    (net (code "122") (name "PA_08") (class "Default")
      (node (ref "J10") (pin "P$25") (pinfunction "P$25_P$25") (pintype "bidirectional"))
    )
    (net (code "123") (name "PA_09") (class "Default")
      (node (ref "J10") (pin "P$24") (pinfunction "P$24_P$24") (pintype "bidirectional"))
    )
    (net (code "124") (name "PA_10") (class "Default")
      (node (ref "J10") (pin "P$23") (pinfunction "P$23_P$23") (pintype "bidirectional"))
    )
    (net (code "125") (name "VDD") (class "Default")
      (node (ref "J1") (pin "3") (pinfunction "3_3") (pintype "passive"))
      (node (ref "J1") (pin "4") (pinfunction "4_4") (pintype "passive"))
      (node (ref "R1") (pin "P$1") (pinfunction "1_P$1") (pintype "passive"))
      (node (ref "R10") (pin "P$1") (pinfunction "1_P$1") (pintype "passive"))
      (node (ref "R11") (pin "P$1") (pinfunction "1_P$1") (pintype "passive"))
      (node (ref "R12") (pin "P$1") (pinfunction "1_P$1") (pintype "passive"))
      (node (ref "R13") (pin "P$2") (pinfunction "2_P$2") (pintype "passive"))
      (node (ref "R14") (pin "P$1") (pinfunction "1_P$1") (pintype "passive"))
      (node (ref "R15") (pin "P$1") (pinfunction "1_P$1") (pintype "passive"))
      (node (ref "R16") (pin "P$1") (pinfunction "1_P$1") (pintype "passive"))
      (node (ref "R17") (pin "P$1") (pinfunction "1_P$1") (pintype "passive"))
      (node (ref "R2") (pin "P$1") (pinfunction "1_P$1") (pintype "passive"))
      (node (ref "R23") (pin "P$2") (pinfunction "2_P$2") (pintype "passive"))
      (node (ref "R24") (pin "P$2") (pinfunction "2_P$2") (pintype "passive"))
      (node (ref "R25") (pin "P$2") (pinfunction "2_P$2") (pintype "passive"))
      (node (ref "R26") (pin "P$2") (pinfunction "2_P$2") (pintype "passive"))
      (node (ref "R27") (pin "P$2") (pinfunction "2_P$2") (pintype "passive"))
      (node (ref "R28") (pin "P$2") (pinfunction "2_P$2") (pintype "passive"))
      (node (ref "R29") (pin "P$2") (pinfunction "2_P$2") (pintype "passive"))
      (node (ref "R3") (pin "P$1") (pinfunction "1_P$1") (pintype "passive"))
      (node (ref "R30") (pin "P$2") (pinfunction "2_P$2") (pintype "passive"))
      (node (ref "R32") (pin "P$2") (pinfunction "2_P$2") (pintype "passive"))
      (node (ref "R34") (pin "P$2") (pinfunction "2_P$2") (pintype "passive"))
      (node (ref "R4") (pin "P$1") (pinfunction "1_P$1") (pintype "passive"))
      (node (ref "R5") (pin "P$1") (pinfunction "1_P$1") (pintype "passive"))
      (node (ref "R6") (pin "P$1") (pinfunction "1_P$1") (pintype "passive"))
      (node (ref "R7") (pin "P$1") (pinfunction "1_P$1") (pintype "passive"))
      (node (ref "R8") (pin "P$1") (pinfunction "1_P$1") (pintype "passive"))
      (node (ref "R9") (pin "P$1") (pinfunction "1_P$1") (pintype "passive"))
    )
    (net (code "126") (name "VDD5") (class "Default")
      (node (ref "J1") (pin "5") (pinfunction "5_5") (pintype "passive"))
      (node (ref "J1") (pin "6") (pinfunction "6_6") (pintype "passive"))
    )
    (net (code "127") (name "VDD12") (class "Default")
      (node (ref "J1") (pin "7") (pinfunction "7_7") (pintype "passive"))
      (node (ref "J1") (pin "8") (pinfunction "8_8") (pintype "passive"))
    )
  )
)
